# 1_040_1573_rev01_highside.net
KiCad netlist of a schematic drawn in Altium Designer
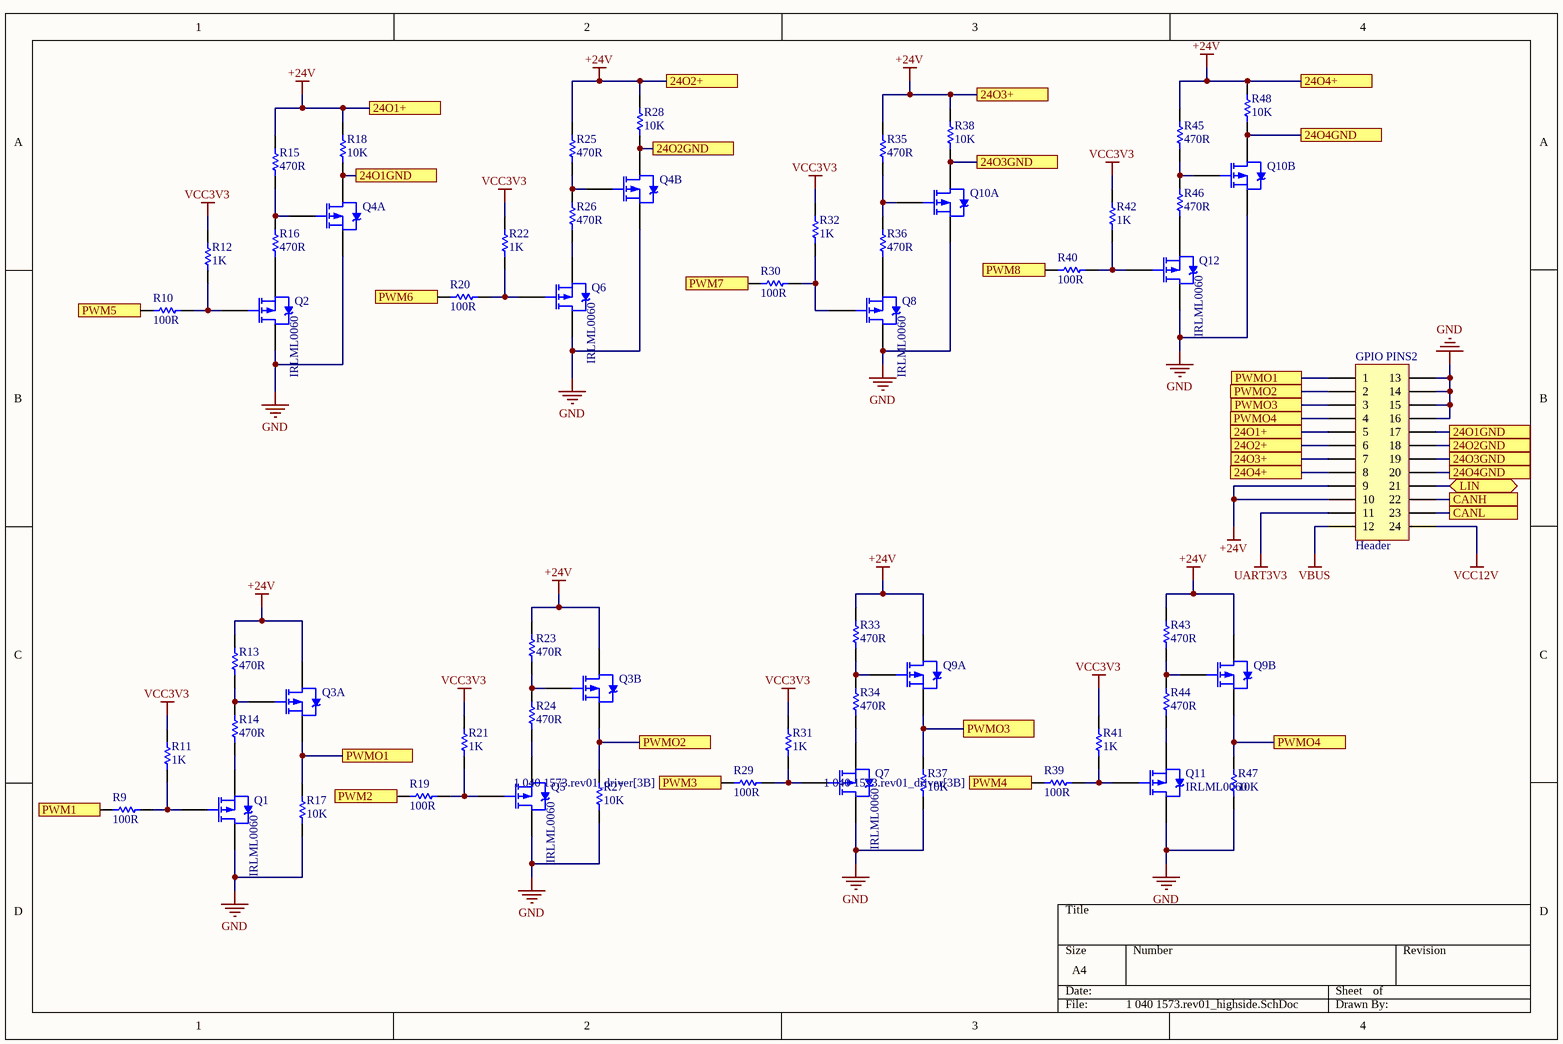
[diagram p0: 1 040 1573.rev01_highside.SchDoc]

(export (version "E")
  (design (tool "Eeschema 10.0.6"))
  (components
    (comp (ref "GPIO PINS2")
      (value "Header")
      (footprint "HDR2X12_CEN")
      (description "Header, 12-Pin, Dual row")
      (fields (field (name "PUBLISHER") "Altium Limited"))
      (libsource (lib "Sanel_Lib_V1") (part "Header 12X2A"))
    )
    (comp (ref "Q1")
      (value "IRLML0060")
      (footprint "SOT_23")
      (description "1 045 0018")
      (fields
        (field (name "MANUFACTURER") "Infineon Technologies")
        (field (name "PUBLISHER") "Altium Limited")
      )
      (libsource (lib "Sanel_Lib_V1") (part "MOSFET_SMD_NCH_60V_2.7A_SOT23_INFINEON_IRLML0060"))
    )
    (comp (ref "Q2")
      (value "IRLML0060")
      (footprint "SOT_23")
      (description "1 045 0018")
      (fields
        (field (name "MANUFACTURER") "Infineon Technologies")
        (field (name "PUBLISHER") "Altium Limited")
      )
      (libsource (lib "Sanel_Lib_V1") (part "MOSFET_SMD_NCH_60V_2.7A_SOT23_INFINEON_IRLML0060"))
    )
    (comp (ref "Q3")
      (value "MOSFET_SMD_2PCH_55V_3.4A_SO8_INFINEON_IRF7342")
      (footprint "SO-8")
      (description "1 045 0014")
      (fields
        (field (name "MANUFACTURER") "Infineon Technologies")
        (field (name "PUBLISHER") "Altium Limited")
      )
      (libsource (lib "Sanel_Lib_V1") (part "MOSFET_SMD_2PCH_55V_3.4A_SO8_INFINEON_IRF7342"))
    )
    (comp (ref "Q4")
      (value "MOSFET_SMD_2PCH_55V_3.4A_SO8_INFINEON_IRF7342")
      (footprint "SO-8")
      (description "1 045 0014")
      (fields
        (field (name "MANUFACTURER") "Infineon Technologies")
        (field (name "PUBLISHER") "Altium Limited")
      )
      (libsource (lib "Sanel_Lib_V1") (part "MOSFET_SMD_2PCH_55V_3.4A_SO8_INFINEON_IRF7342"))
    )
    (comp (ref "Q5")
      (value "IRLML0060")
      (footprint "SOT_23")
      (description "1 045 0018")
      (fields
        (field (name "MANUFACTURER") "Infineon Technologies")
        (field (name "PUBLISHER") "Altium Limited")
      )
      (libsource (lib "Sanel_Lib_V1") (part "MOSFET_SMD_NCH_60V_2.7A_SOT23_INFINEON_IRLML0060"))
    )
    (comp (ref "Q6")
      (value "IRLML0060")
      (footprint "SOT_23")
      (description "1 045 0018")
      (fields
        (field (name "MANUFACTURER") "Infineon Technologies")
        (field (name "PUBLISHER") "Altium Limited")
      )
      (libsource (lib "Sanel_Lib_V1") (part "MOSFET_SMD_NCH_60V_2.7A_SOT23_INFINEON_IRLML0060"))
    )
    (comp (ref "Q7")
      (value "IRLML0060")
      (footprint "SOT_23")
      (description "1 045 0018")
      (fields
        (field (name "MANUFACTURER") "Infineon Technologies")
        (field (name "PUBLISHER") "Altium Limited")
      )
      (libsource (lib "Sanel_Lib_V1") (part "MOSFET_SMD_NCH_60V_2.7A_SOT23_INFINEON_IRLML0060"))
    )
    (comp (ref "Q8")
      (value "IRLML0060")
      (footprint "SOT_23")
      (description "1 045 0018")
      (fields
        (field (name "MANUFACTURER") "Infineon Technologies")
        (field (name "PUBLISHER") "Altium Limited")
      )
      (libsource (lib "Sanel_Lib_V1") (part "MOSFET_SMD_NCH_60V_2.7A_SOT23_INFINEON_IRLML0060"))
    )
    (comp (ref "Q9")
      (value "MOSFET_SMD_2PCH_55V_3.4A_SO8_INFINEON_IRF7342")
      (footprint "SO-8")
      (description "1 045 0014")
      (fields
        (field (name "MANUFACTURER") "Infineon Technologies")
        (field (name "PUBLISHER") "Altium Limited")
      )
      (libsource (lib "Sanel_Lib_V1") (part "MOSFET_SMD_2PCH_55V_3.4A_SO8_INFINEON_IRF7342"))
    )
    (comp (ref "Q10")
      (value "MOSFET_SMD_2PCH_55V_3.4A_SO8_INFINEON_IRF7342")
      (footprint "SO-8")
      (description "1 045 0014")
      (fields
        (field (name "MANUFACTURER") "Infineon Technologies")
        (field (name "PUBLISHER") "Altium Limited")
      )
      (libsource (lib "Sanel_Lib_V1") (part "MOSFET_SMD_2PCH_55V_3.4A_SO8_INFINEON_IRF7342"))
    )
    (comp (ref "Q11")
      (value "IRLML0060")
      (footprint "SOT_23")
      (description "1 045 0018")
      (fields
        (field (name "MANUFACTURER") "Infineon Technologies")
        (field (name "PUBLISHER") "Altium Limited")
      )
      (libsource (lib "Sanel_Lib_V1") (part "MOSFET_SMD_NCH_60V_2.7A_SOT23_INFINEON_IRLML0060"))
    )
    (comp (ref "Q12")
      (value "IRLML0060")
      (footprint "SOT_23")
      (description "1 045 0018")
      (fields
        (field (name "MANUFACTURER") "Infineon Technologies")
        (field (name "PUBLISHER") "Altium Limited")
      )
      (libsource (lib "Sanel_Lib_V1") (part "MOSFET_SMD_NCH_60V_2.7A_SOT23_INFINEON_IRLML0060"))
    )
    (comp (ref "R9")
      (value "100R")
      (footprint "Resistor(0603) -1")
      (description "1 042 0269")
      (fields (field (name "PUBLISHER") "Altium Limited"))
      (libsource (lib "Sanel_Lib_V1") (part "RES_SMD_100R_%1_0603_AEC"))
    )
    (comp (ref "R10")
      (value "100R")
      (footprint "Resistor(0603) -1")
      (description "1 042 0269")
      (fields (field (name "PUBLISHER") "Altium Limited"))
      (libsource (lib "Sanel_Lib_V1") (part "RES_SMD_100R_%1_0603_AEC"))
    )
    (comp (ref "R11")
      (value "1K")
      (footprint "Resistor(0603) -1")
      (description "1 042 0331")
      (fields (field (name "PUBLISHER") "Altium Limited"))
      (libsource (lib "Sanel_Lib_V1") (part "RES_SMD_1K_%1_0603_AEC"))
    )
    (comp (ref "R12")
      (value "1K")
      (footprint "Resistor(0603) -1")
      (description "1 042 0331")
      (fields (field (name "PUBLISHER") "Altium Limited"))
      (libsource (lib "Sanel_Lib_V1") (part "RES_SMD_1K_%1_0603_AEC"))
    )
    (comp (ref "R13")
      (value "470R")
      (footprint "Resistor(0805) -1")
      (description "1 042 0476")
      (fields (field (name "PUBLISHER") "Altium Limited"))
      (libsource (lib "Sanel_Lib_V1") (part "RES_SMD_470R_%1_0805"))
    )
    (comp (ref "R14")
      (value "470R")
      (footprint "Resistor(0805) -1")
      (description "1 042 0476")
      (fields (field (name "PUBLISHER") "Altium Limited"))
      (libsource (lib "Sanel_Lib_V1") (part "RES_SMD_470R_%1_0805"))
    )
    (comp (ref "R15")
      (value "470R")
      (footprint "Resistor(0805) -1")
      (description "1 042 0476")
      (fields (field (name "PUBLISHER") "Altium Limited"))
      (libsource (lib "Sanel_Lib_V1") (part "RES_SMD_470R_%1_0805"))
    )
    (comp (ref "R16")
      (value "470R")
      (footprint "Resistor(0805) -1")
      (description "1 042 0476")
      (fields (field (name "PUBLISHER") "Altium Limited"))
      (libsource (lib "Sanel_Lib_V1") (part "RES_SMD_470R_%1_0805"))
    )
    (comp (ref "R17")
      (value "10K")
      (footprint "Resistor(0805) -1")
      (description "1 042 0278")
      (fields (field (name "PUBLISHER") "Altium Limited"))
      (libsource (lib "Sanel_Lib_V1") (part "RES_SMD_10K_%1_0805"))
    )
    (comp (ref "R18")
      (value "10K")
      (footprint "Resistor(0805) -1")
      (description "1 042 0278")
      (fields (field (name "PUBLISHER") "Altium Limited"))
      (libsource (lib "Sanel_Lib_V1") (part "RES_SMD_10K_%1_0805"))
    )
    (comp (ref "R19")
      (value "100R")
      (footprint "Resistor(0603) -1")
      (description "1 042 0269")
      (fields (field (name "PUBLISHER") "Altium Limited"))
      (libsource (lib "Sanel_Lib_V1") (part "RES_SMD_100R_%1_0603_AEC"))
    )
    (comp (ref "R20")
      (value "100R")
      (footprint "Resistor(0603) -1")
      (description "1 042 0269")
      (fields (field (name "PUBLISHER") "Altium Limited"))
      (libsource (lib "Sanel_Lib_V1") (part "RES_SMD_100R_%1_0603_AEC"))
    )
    (comp (ref "R21")
      (value "1K")
      (footprint "Resistor(0603) -1")
      (description "1 042 0331")
      (fields (field (name "PUBLISHER") "Altium Limited"))
      (libsource (lib "Sanel_Lib_V1") (part "RES_SMD_1K_%1_0603_AEC"))
    )
    (comp (ref "R22")
      (value "1K")
      (footprint "Resistor(0603) -1")
      (description "1 042 0331")
      (fields (field (name "PUBLISHER") "Altium Limited"))
      (libsource (lib "Sanel_Lib_V1") (part "RES_SMD_1K_%1_0603_AEC"))
    )
    (comp (ref "R23")
      (value "470R")
      (footprint "Resistor(0805) -1")
      (description "1 042 0476")
      (fields (field (name "PUBLISHER") "Altium Limited"))
      (libsource (lib "Sanel_Lib_V1") (part "RES_SMD_470R_%1_0805"))
    )
    (comp (ref "R24")
      (value "470R")
      (footprint "Resistor(0805) -1")
      (description "1 042 0476")
      (fields (field (name "PUBLISHER") "Altium Limited"))
      (libsource (lib "Sanel_Lib_V1") (part "RES_SMD_470R_%1_0805"))
    )
    (comp (ref "R25")
      (value "470R")
      (footprint "Resistor(0805) -1")
      (description "1 042 0476")
      (fields (field (name "PUBLISHER") "Altium Limited"))
      (libsource (lib "Sanel_Lib_V1") (part "RES_SMD_470R_%1_0805"))
    )
    (comp (ref "R26")
      (value "470R")
      (footprint "Resistor(0805) -1")
      (description "1 042 0476")
      (fields (field (name "PUBLISHER") "Altium Limited"))
      (libsource (lib "Sanel_Lib_V1") (part "RES_SMD_470R_%1_0805"))
    )
    (comp (ref "R27")
      (value "10K")
      (footprint "Resistor(0805) -1")
      (description "1 042 0278")
      (fields (field (name "PUBLISHER") "Altium Limited"))
      (libsource (lib "Sanel_Lib_V1") (part "RES_SMD_10K_%1_0805"))
    )
    (comp (ref "R28")
      (value "10K")
      (footprint "Resistor(0805) -1")
      (description "1 042 0278")
      (fields (field (name "PUBLISHER") "Altium Limited"))
      (libsource (lib "Sanel_Lib_V1") (part "RES_SMD_10K_%1_0805"))
    )
    (comp (ref "R29")
      (value "100R")
      (footprint "Resistor(0603) -1")
      (description "1 042 0269")
      (fields (field (name "PUBLISHER") "Altium Limited"))
      (libsource (lib "Sanel_Lib_V1") (part "RES_SMD_100R_%1_0603_AEC"))
    )
    (comp (ref "R30")
      (value "100R")
      (footprint "Resistor(0603) -1")
      (description "1 042 0269")
      (fields (field (name "PUBLISHER") "Altium Limited"))
      (libsource (lib "Sanel_Lib_V1") (part "RES_SMD_100R_%1_0603_AEC"))
    )
    (comp (ref "R31")
      (value "1K")
      (footprint "Resistor(0603) -1")
      (description "1 042 0331")
      (fields (field (name "PUBLISHER") "Altium Limited"))
      (libsource (lib "Sanel_Lib_V1") (part "RES_SMD_1K_%1_0603_AEC"))
    )
    (comp (ref "R32")
      (value "1K")
      (footprint "Resistor(0603) -1")
      (description "1 042 0331")
      (fields (field (name "PUBLISHER") "Altium Limited"))
      (libsource (lib "Sanel_Lib_V1") (part "RES_SMD_1K_%1_0603_AEC"))
    )
    (comp (ref "R33")
      (value "470R")
      (footprint "Resistor(0805) -1")
      (description "1 042 0476")
      (fields (field (name "PUBLISHER") "Altium Limited"))
      (libsource (lib "Sanel_Lib_V1") (part "RES_SMD_470R_%1_0805"))
    )
    (comp (ref "R34")
      (value "470R")
      (footprint "Resistor(0805) -1")
      (description "1 042 0476")
      (fields (field (name "PUBLISHER") "Altium Limited"))
      (libsource (lib "Sanel_Lib_V1") (part "RES_SMD_470R_%1_0805"))
    )
    (comp (ref "R35")
      (value "470R")
      (footprint "Resistor(0805) -1")
      (description "1 042 0476")
      (fields (field (name "PUBLISHER") "Altium Limited"))
      (libsource (lib "Sanel_Lib_V1") (part "RES_SMD_470R_%1_0805"))
    )
    (comp (ref "R36")
      (value "470R")
      (footprint "Resistor(0805) -1")
      (description "1 042 0476")
      (fields (field (name "PUBLISHER") "Altium Limited"))
      (libsource (lib "Sanel_Lib_V1") (part "RES_SMD_470R_%1_0805"))
    )
    (comp (ref "R37")
      (value "10K")
      (footprint "Resistor(0805) -1")
      (description "1 042 0278")
      (fields (field (name "PUBLISHER") "Altium Limited"))
      (libsource (lib "Sanel_Lib_V1") (part "RES_SMD_10K_%1_0805"))
    )
    (comp (ref "R38")
      (value "10K")
      (footprint "Resistor(0805) -1")
      (description "1 042 0278")
      (fields (field (name "PUBLISHER") "Altium Limited"))
      (libsource (lib "Sanel_Lib_V1") (part "RES_SMD_10K_%1_0805"))
    )
    (comp (ref "R39")
      (value "100R")
      (footprint "Resistor(0603) -1")
      (description "1 042 0269")
      (fields (field (name "PUBLISHER") "Altium Limited"))
      (libsource (lib "Sanel_Lib_V1") (part "RES_SMD_100R_%1_0603_AEC"))
    )
    (comp (ref "R40")
      (value "100R")
      (footprint "Resistor(0603) -1")
      (description "1 042 0269")
      (fields (field (name "PUBLISHER") "Altium Limited"))
      (libsource (lib "Sanel_Lib_V1") (part "RES_SMD_100R_%1_0603_AEC"))
    )
    (comp (ref "R41")
      (value "1K")
      (footprint "Resistor(0603) -1")
      (description "1 042 0331")
      (fields (field (name "PUBLISHER") "Altium Limited"))
      (libsource (lib "Sanel_Lib_V1") (part "RES_SMD_1K_%1_0603_AEC"))
    )
    (comp (ref "R42")
      (value "1K")
      (footprint "Resistor(0603) -1")
      (description "1 042 0331")
      (fields (field (name "PUBLISHER") "Altium Limited"))
      (libsource (lib "Sanel_Lib_V1") (part "RES_SMD_1K_%1_0603_AEC"))
    )
    (comp (ref "R43")
      (value "470R")
      (footprint "Resistor(0805) -1")
      (description "1 042 0476")
      (fields (field (name "PUBLISHER") "Altium Limited"))
      (libsource (lib "Sanel_Lib_V1") (part "RES_SMD_470R_%1_0805"))
    )
    (comp (ref "R44")
      (value "470R")
      (footprint "Resistor(0805) -1")
      (description "1 042 0476")
      (fields (field (name "PUBLISHER") "Altium Limited"))
      (libsource (lib "Sanel_Lib_V1") (part "RES_SMD_470R_%1_0805"))
    )
    (comp (ref "R45")
      (value "470R")
      (footprint "Resistor(0805) -1")
      (description "1 042 0476")
      (fields (field (name "PUBLISHER") "Altium Limited"))
      (libsource (lib "Sanel_Lib_V1") (part "RES_SMD_470R_%1_0805"))
    )
    (comp (ref "R46")
      (value "470R")
      (footprint "Resistor(0805) -1")
      (description "1 042 0476")
      (fields (field (name "PUBLISHER") "Altium Limited"))
      (libsource (lib "Sanel_Lib_V1") (part "RES_SMD_470R_%1_0805"))
    )
    (comp (ref "R47")
      (value "10K")
      (footprint "Resistor(0805) -1")
      (description "1 042 0278")
      (fields (field (name "PUBLISHER") "Altium Limited"))
      (libsource (lib "Sanel_Lib_V1") (part "RES_SMD_10K_%1_0805"))
    )
    (comp (ref "R48")
      (value "10K")
      (footprint "Resistor(0805) -1")
      (description "1 042 0278")
      (fields (field (name "PUBLISHER") "Altium Limited"))
      (libsource (lib "Sanel_Lib_V1") (part "RES_SMD_10K_%1_0805"))
    )
  )
  (nets
    (net (code "1") (name "+24V") (class "Default")
      (node (ref "GPIO PINS2") (pin "10") (pinfunction "10_10") (pintype "passive"))
      (node (ref "GPIO PINS2") (pin "5") (pinfunction "5_5") (pintype "passive"))
      (node (ref "GPIO PINS2") (pin "6") (pinfunction "6_6") (pintype "passive"))
      (node (ref "GPIO PINS2") (pin "7") (pinfunction "7_7") (pintype "passive"))
      (node (ref "GPIO PINS2") (pin "8") (pinfunction "8_8") (pintype "passive"))
      (node (ref "GPIO PINS2") (pin "9") (pinfunction "9_9") (pintype "passive"))
      (node (ref "Q3") (pin "6") (pinfunction "D2_6") (pintype "passive"))
      (node (ref "Q3") (pin "7") (pinfunction "D1_7") (pintype "passive"))
      (node (ref "Q9") (pin "6") (pinfunction "D2_6") (pintype "passive"))
      (node (ref "Q9") (pin "7") (pinfunction "D1_7") (pintype "passive"))
      (node (ref "R13") (pin "2") (pinfunction "2_2") (pintype "passive"))
      (node (ref "R15") (pin "2") (pinfunction "2_2") (pintype "passive"))
      (node (ref "R18") (pin "2") (pinfunction "2_2") (pintype "passive"))
      (node (ref "R23") (pin "2") (pinfunction "2_2") (pintype "passive"))
      (node (ref "R25") (pin "2") (pinfunction "2_2") (pintype "passive"))
      (node (ref "R28") (pin "2") (pinfunction "2_2") (pintype "passive"))
      (node (ref "R33") (pin "2") (pinfunction "2_2") (pintype "passive"))
      (node (ref "R35") (pin "2") (pinfunction "2_2") (pintype "passive"))
      (node (ref "R38") (pin "2") (pinfunction "2_2") (pintype "passive"))
      (node (ref "R43") (pin "2") (pinfunction "2_2") (pintype "passive"))
      (node (ref "R45") (pin "2") (pinfunction "2_2") (pintype "passive"))
      (node (ref "R48") (pin "2") (pinfunction "2_2") (pintype "passive"))
    )
    (net (code "2") (name "/24O1GND") (class "Default")
      (node (ref "GPIO PINS2") (pin "17") (pinfunction "17_17") (pintype "passive"))
      (node (ref "Q4") (pin "7") (pinfunction "D1_7") (pintype "passive"))
      (node (ref "R18") (pin "1") (pinfunction "1_1") (pintype "passive"))
    )
    (net (code "3") (name "/24O2GND") (class "Default")
      (node (ref "GPIO PINS2") (pin "18") (pinfunction "18_18") (pintype "passive"))
      (node (ref "Q4") (pin "6") (pinfunction "D2_6") (pintype "passive"))
      (node (ref "R28") (pin "1") (pinfunction "1_1") (pintype "passive"))
    )
    (net (code "4") (name "/24O3GND") (class "Default")
      (node (ref "GPIO PINS2") (pin "19") (pinfunction "19_19") (pintype "passive"))
      (node (ref "Q10") (pin "7") (pinfunction "D1_7") (pintype "passive"))
      (node (ref "R38") (pin "1") (pinfunction "1_1") (pintype "passive"))
    )
    (net (code "5") (name "/24O4GND") (class "Default")
      (node (ref "GPIO PINS2") (pin "20") (pinfunction "20_20") (pintype "passive"))
      (node (ref "Q10") (pin "6") (pinfunction "D2_6") (pintype "passive"))
      (node (ref "R48") (pin "1") (pinfunction "1_1") (pintype "passive"))
    )
    (net (code "6") (name "/CANH") (class "Default")
      (node (ref "GPIO PINS2") (pin "22") (pinfunction "22_22") (pintype "passive"))
    )
    (net (code "7") (name "/CANL") (class "Default")
      (node (ref "GPIO PINS2") (pin "23") (pinfunction "23_23") (pintype "passive"))
    )
    (net (code "8") (name "/LIN") (class "Default")
      (node (ref "GPIO PINS2") (pin "21") (pinfunction "21_21") (pintype "passive"))
    )
    (net (code "9") (name "/PWM1") (class "Default")
      (node (ref "R9") (pin "1") (pinfunction "1_1") (pintype "passive"))
    )
    (net (code "10") (name "/PWM2") (class "Default")
      (node (ref "R19") (pin "1") (pinfunction "1_1") (pintype "passive"))
    )
    (net (code "11") (name "/PWM3") (class "Default")
      (node (ref "R29") (pin "1") (pinfunction "1_1") (pintype "passive"))
    )
    (net (code "12") (name "/PWM4") (class "Default")
      (node (ref "R39") (pin "1") (pinfunction "1_1") (pintype "passive"))
    )
    (net (code "13") (name "/PWM5") (class "Default")
      (node (ref "R10") (pin "1") (pinfunction "1_1") (pintype "passive"))
    )
    (net (code "14") (name "/PWM6") (class "Default")
      (node (ref "R20") (pin "1") (pinfunction "1_1") (pintype "passive"))
    )
    (net (code "15") (name "/PWM7") (class "Default")
      (node (ref "R30") (pin "1") (pinfunction "1_1") (pintype "passive"))
    )
    (net (code "16") (name "/PWM8") (class "Default")
      (node (ref "R40") (pin "1") (pinfunction "1_1") (pintype "passive"))
    )
    (net (code "17") (name "/PWMO1") (class "Default")
      (node (ref "GPIO PINS2") (pin "1") (pinfunction "1_1") (pintype "passive"))
      (node (ref "Q3") (pin "1") (pinfunction "S1_1") (pintype "passive"))
      (node (ref "R17") (pin "2") (pinfunction "2_2") (pintype "passive"))
    )
    (net (code "18") (name "/PWMO2") (class "Default")
      (node (ref "GPIO PINS2") (pin "2") (pinfunction "2_2") (pintype "passive"))
      (node (ref "Q3") (pin "3") (pinfunction "S2_3") (pintype "passive"))
      (node (ref "R27") (pin "2") (pinfunction "2_2") (pintype "passive"))
    )
    (net (code "19") (name "/PWMO3") (class "Default")
      (node (ref "GPIO PINS2") (pin "3") (pinfunction "3_3") (pintype "passive"))
      (node (ref "Q9") (pin "1") (pinfunction "S1_1") (pintype "passive"))
      (node (ref "R37") (pin "2") (pinfunction "2_2") (pintype "passive"))
    )
    (net (code "20") (name "/PWMO4") (class "Default")
      (node (ref "GPIO PINS2") (pin "4") (pinfunction "4_4") (pintype "passive"))
      (node (ref "Q9") (pin "3") (pinfunction "S2_3") (pintype "passive"))
      (node (ref "R47") (pin "2") (pinfunction "2_2") (pintype "passive"))
    )
    (net (code "21") (name "GND") (class "Default")
      (node (ref "GPIO PINS2") (pin "13") (pinfunction "13_13") (pintype "passive"))
      (node (ref "GPIO PINS2") (pin "14") (pinfunction "14_14") (pintype "passive"))
      (node (ref "GPIO PINS2") (pin "15") (pinfunction "15_15") (pintype "passive"))
      (node (ref "GPIO PINS2") (pin "16") (pinfunction "16_16") (pintype "passive"))
      (node (ref "Q1") (pin "1") (pinfunction "D_1") (pintype "passive"))
      (node (ref "Q10") (pin "1") (pinfunction "S1_1") (pintype "passive"))
      (node (ref "Q10") (pin "3") (pinfunction "S2_3") (pintype "passive"))
      (node (ref "Q11") (pin "1") (pinfunction "D_1") (pintype "passive"))
      (node (ref "Q12") (pin "1") (pinfunction "D_1") (pintype "passive"))
      (node (ref "Q2") (pin "1") (pinfunction "D_1") (pintype "passive"))
      (node (ref "Q4") (pin "1") (pinfunction "S1_1") (pintype "passive"))
      (node (ref "Q4") (pin "3") (pinfunction "S2_3") (pintype "passive"))
      (node (ref "Q5") (pin "1") (pinfunction "D_1") (pintype "passive"))
      (node (ref "Q6") (pin "1") (pinfunction "D_1") (pintype "passive"))
      (node (ref "Q7") (pin "1") (pinfunction "D_1") (pintype "passive"))
      (node (ref "Q8") (pin "1") (pinfunction "D_1") (pintype "passive"))
      (node (ref "R17") (pin "1") (pinfunction "1_1") (pintype "passive"))
      (node (ref "R27") (pin "1") (pinfunction "1_1") (pintype "passive"))
      (node (ref "R37") (pin "1") (pinfunction "1_1") (pintype "passive"))
      (node (ref "R47") (pin "1") (pinfunction "1_1") (pintype "passive"))
    )
    (net (code "22") (name "Net-(Q1-G)") (class "Default")
      (node (ref "Q1") (pin "2") (pinfunction "G_2") (pintype "passive"))
      (node (ref "R11") (pin "2") (pinfunction "2_2") (pintype "passive"))
      (node (ref "R9") (pin "2") (pinfunction "2_2") (pintype "passive"))
    )
    (net (code "23") (name "Net-(Q1-S)") (class "Default")
      (node (ref "Q1") (pin "3") (pinfunction "S_3") (pintype "passive"))
      (node (ref "R14") (pin "1") (pinfunction "1_1") (pintype "passive"))
    )
    (net (code "24") (name "Net-(Q2-G)") (class "Default")
      (node (ref "Q2") (pin "2") (pinfunction "G_2") (pintype "passive"))
      (node (ref "R10") (pin "2") (pinfunction "2_2") (pintype "passive"))
      (node (ref "R12") (pin "2") (pinfunction "2_2") (pintype "passive"))
    )
    (net (code "25") (name "Net-(Q2-S)") (class "Default")
      (node (ref "Q2") (pin "3") (pinfunction "S_3") (pintype "passive"))
      (node (ref "R16") (pin "1") (pinfunction "1_1") (pintype "passive"))
    )
    (net (code "26") (name "Net-(Q3A-G1)") (class "Default")
      (node (ref "Q3") (pin "2") (pinfunction "G1_2") (pintype "passive"))
      (node (ref "R13") (pin "1") (pinfunction "1_1") (pintype "passive"))
      (node (ref "R14") (pin "2") (pinfunction "2_2") (pintype "passive"))
    )
    (net (code "27") (name "Net-(Q3B-G2)") (class "Default")
      (node (ref "Q3") (pin "4") (pinfunction "G2_4") (pintype "passive"))
      (node (ref "R23") (pin "1") (pinfunction "1_1") (pintype "passive"))
      (node (ref "R24") (pin "2") (pinfunction "2_2") (pintype "passive"))
    )
    (net (code "28") (name "Net-(Q4A-G1)") (class "Default")
      (node (ref "Q4") (pin "2") (pinfunction "G1_2") (pintype "passive"))
      (node (ref "R15") (pin "1") (pinfunction "1_1") (pintype "passive"))
      (node (ref "R16") (pin "2") (pinfunction "2_2") (pintype "passive"))
    )
    (net (code "29") (name "Net-(Q4B-G2)") (class "Default")
      (node (ref "Q4") (pin "4") (pinfunction "G2_4") (pintype "passive"))
      (node (ref "R25") (pin "1") (pinfunction "1_1") (pintype "passive"))
      (node (ref "R26") (pin "2") (pinfunction "2_2") (pintype "passive"))
    )
    (net (code "30") (name "Net-(Q5-G)") (class "Default")
      (node (ref "Q5") (pin "2") (pinfunction "G_2") (pintype "passive"))
      (node (ref "R19") (pin "2") (pinfunction "2_2") (pintype "passive"))
      (node (ref "R21") (pin "2") (pinfunction "2_2") (pintype "passive"))
    )
    (net (code "31") (name "Net-(Q5-S)") (class "Default")
      (node (ref "Q5") (pin "3") (pinfunction "S_3") (pintype "passive"))
      (node (ref "R24") (pin "1") (pinfunction "1_1") (pintype "passive"))
    )
    (net (code "32") (name "Net-(Q6-G)") (class "Default")
      (node (ref "Q6") (pin "2") (pinfunction "G_2") (pintype "passive"))
      (node (ref "R20") (pin "2") (pinfunction "2_2") (pintype "passive"))
      (node (ref "R22") (pin "2") (pinfunction "2_2") (pintype "passive"))
    )
    (net (code "33") (name "Net-(Q6-S)") (class "Default")
      (node (ref "Q6") (pin "3") (pinfunction "S_3") (pintype "passive"))
      (node (ref "R26") (pin "1") (pinfunction "1_1") (pintype "passive"))
    )
    (net (code "34") (name "Net-(Q7-G)") (class "Default")
      (node (ref "Q7") (pin "2") (pinfunction "G_2") (pintype "passive"))
      (node (ref "R29") (pin "2") (pinfunction "2_2") (pintype "passive"))
      (node (ref "R31") (pin "2") (pinfunction "2_2") (pintype "passive"))
    )
    (net (code "35") (name "Net-(Q7-S)") (class "Default")
      (node (ref "Q7") (pin "3") (pinfunction "S_3") (pintype "passive"))
      (node (ref "R34") (pin "1") (pinfunction "1_1") (pintype "passive"))
    )
    (net (code "36") (name "Net-(Q8-G)") (class "Default")
      (node (ref "Q8") (pin "2") (pinfunction "G_2") (pintype "passive"))
      (node (ref "R30") (pin "2") (pinfunction "2_2") (pintype "passive"))
      (node (ref "R32") (pin "2") (pinfunction "2_2") (pintype "passive"))
    )
    (net (code "37") (name "Net-(Q8-S)") (class "Default")
      (node (ref "Q8") (pin "3") (pinfunction "S_3") (pintype "passive"))
      (node (ref "R36") (pin "1") (pinfunction "1_1") (pintype "passive"))
    )
    (net (code "38") (name "Net-(Q9A-G1)") (class "Default")
      (node (ref "Q9") (pin "2") (pinfunction "G1_2") (pintype "passive"))
      (node (ref "R33") (pin "1") (pinfunction "1_1") (pintype "passive"))
      (node (ref "R34") (pin "2") (pinfunction "2_2") (pintype "passive"))
    )
    (net (code "39") (name "Net-(Q9B-G2)") (class "Default")
      (node (ref "Q9") (pin "4") (pinfunction "G2_4") (pintype "passive"))
      (node (ref "R43") (pin "1") (pinfunction "1_1") (pintype "passive"))
      (node (ref "R44") (pin "2") (pinfunction "2_2") (pintype "passive"))
    )
    (net (code "40") (name "Net-(Q10A-G1)") (class "Default")
      (node (ref "Q10") (pin "2") (pinfunction "G1_2") (pintype "passive"))
      (node (ref "R35") (pin "1") (pinfunction "1_1") (pintype "passive"))
      (node (ref "R36") (pin "2") (pinfunction "2_2") (pintype "passive"))
    )
    (net (code "41") (name "Net-(Q10B-G2)") (class "Default")
      (node (ref "Q10") (pin "4") (pinfunction "G2_4") (pintype "passive"))
      (node (ref "R45") (pin "1") (pinfunction "1_1") (pintype "passive"))
      (node (ref "R46") (pin "2") (pinfunction "2_2") (pintype "passive"))
    )
    (net (code "42") (name "Net-(Q11-G)") (class "Default")
      (node (ref "Q11") (pin "2") (pinfunction "G_2") (pintype "passive"))
      (node (ref "R39") (pin "2") (pinfunction "2_2") (pintype "passive"))
      (node (ref "R41") (pin "2") (pinfunction "2_2") (pintype "passive"))
    )
    (net (code "43") (name "Net-(Q11-S)") (class "Default")
      (node (ref "Q11") (pin "3") (pinfunction "S_3") (pintype "passive"))
      (node (ref "R44") (pin "1") (pinfunction "1_1") (pintype "passive"))
    )
    (net (code "44") (name "Net-(Q12-G)") (class "Default")
      (node (ref "Q12") (pin "2") (pinfunction "G_2") (pintype "passive"))
      (node (ref "R40") (pin "2") (pinfunction "2_2") (pintype "passive"))
      (node (ref "R42") (pin "2") (pinfunction "2_2") (pintype "passive"))
    )
    (net (code "45") (name "Net-(Q12-S)") (class "Default")
      (node (ref "Q12") (pin "3") (pinfunction "S_3") (pintype "passive"))
      (node (ref "R46") (pin "1") (pinfunction "1_1") (pintype "passive"))
    )
    (net (code "46") (name "UART3V3") (class "Default")
      (node (ref "GPIO PINS2") (pin "11") (pinfunction "11_11") (pintype "passive"))
    )
    (net (code "47") (name "VBUS") (class "Default")
      (node (ref "GPIO PINS2") (pin "12") (pinfunction "12_12") (pintype "passive"))
    )
    (net (code "48") (name "VCC3V3") (class "Default")
      (node (ref "R11") (pin "1") (pinfunction "1_1") (pintype "passive"))
      (node (ref "R12") (pin "1") (pinfunction "1_1") (pintype "passive"))
      (node (ref "R21") (pin "1") (pinfunction "1_1") (pintype "passive"))
      (node (ref "R22") (pin "1") (pinfunction "1_1") (pintype "passive"))
      (node (ref "R31") (pin "1") (pinfunction "1_1") (pintype "passive"))
      (node (ref "R32") (pin "1") (pinfunction "1_1") (pintype "passive"))
      (node (ref "R41") (pin "1") (pinfunction "1_1") (pintype "passive"))
      (node (ref "R42") (pin "1") (pinfunction "1_1") (pintype "passive"))
    )
    (net (code "49") (name "VCC12V") (class "Default")
      (node (ref "GPIO PINS2") (pin "24") (pinfunction "24_24") (pintype "passive"))
    )
  )
)
